# Sheet2.net
KiCad netlist of a schematic drawn in Altium Designer
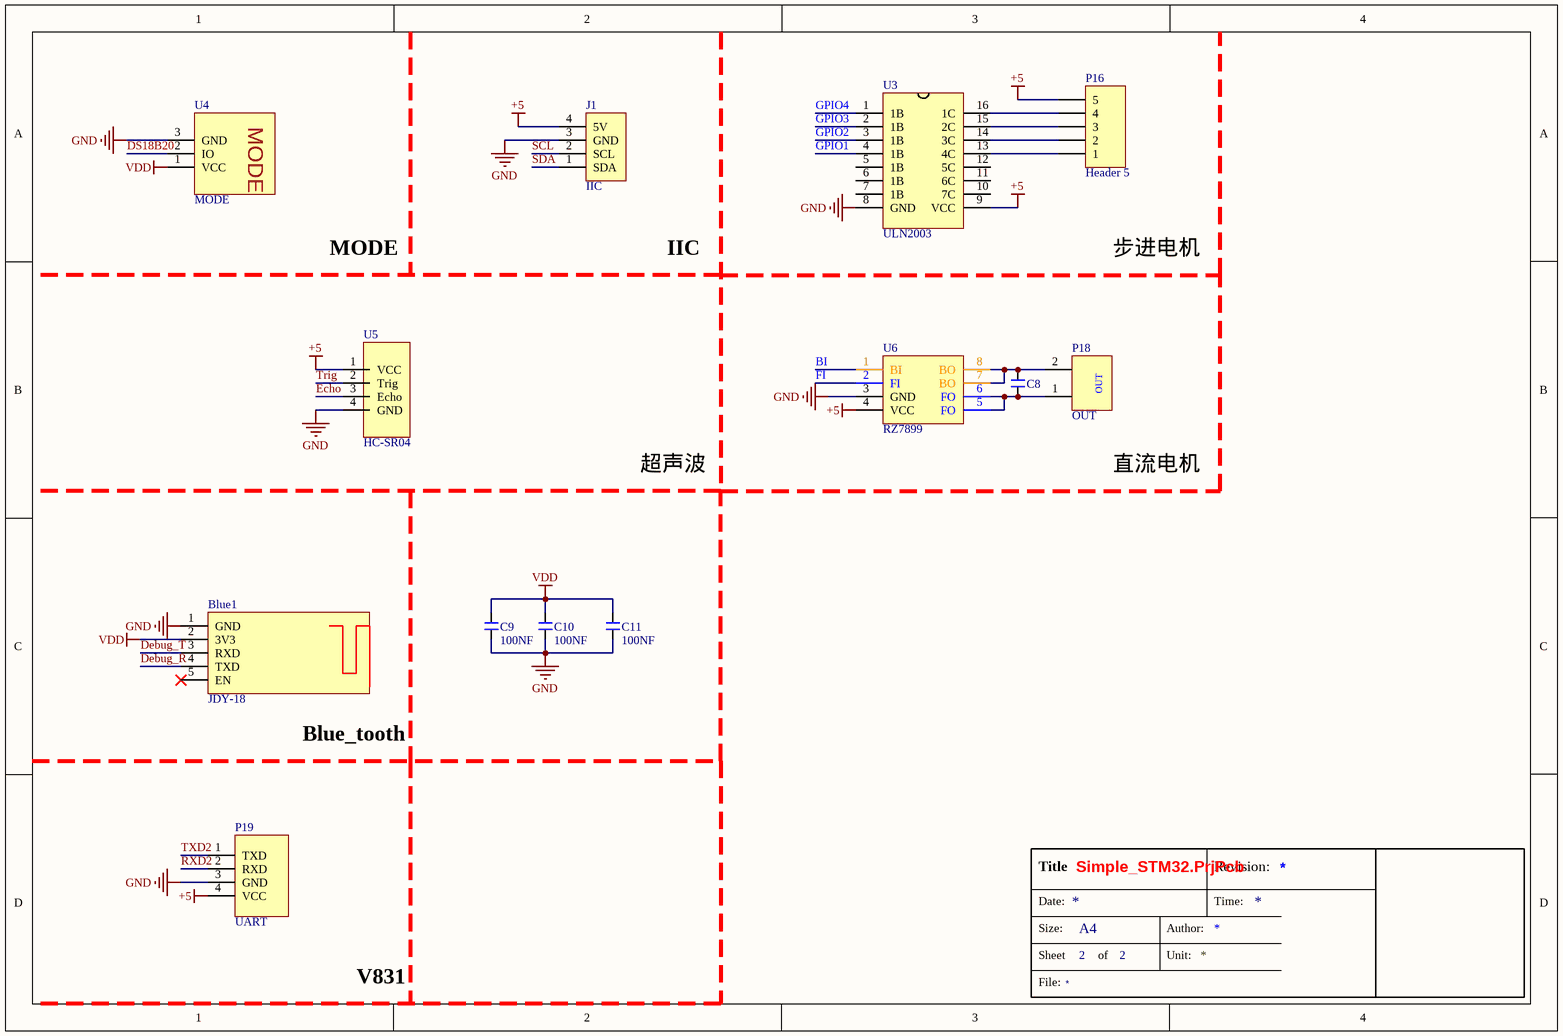
[diagram p0: Sheet2.SchDoc]

(export (version "E")
  (design (tool "Eeschema 10.0.6"))
  (components
    (comp (ref "Blue1")
      (value "JDY-18")
      (footprint "uart-Haerd")
      (description "MODE")
      (libsource (lib "User") (part "JDY-18"))
    )
    (comp (ref "C8")
      (value "100NF")
      (footprint "CAP_0603")
      (description "CAP  12~50V")
      (libsource (lib "User") (part "CAP"))
    )
    (comp (ref "C9")
      (value "100NF")
      (footprint "CAP_0603")
      (description "CAP  12~50V")
      (libsource (lib "User") (part "CAP"))
    )
    (comp (ref "C10")
      (value "100NF")
      (footprint "CAP_0603")
      (description "CAP  12~50V")
      (libsource (lib "User") (part "CAP"))
    )
    (comp (ref "C11")
      (value "100NF")
      (footprint "CAP_0603")
      (description "CAP  12~50V")
      (libsource (lib "User") (part "CAP"))
    )
    (comp (ref "J1")
      (value "IIC")
      (footprint "IIC-XH2.54-4PIN")
      (description "Heard")
      (libsource (lib "User") (part "IIC"))
    )
    (comp (ref "P16")
      (value "Header 5")
      (footprint "XH2.54-WI-5P")
      (description "Header, 5-Pin")
      (fields (field (name "PUBLISHER") "Altium Limited"))
      (libsource (lib "Miscellaneous Connectors") (part "Header 5"))
    )
    (comp (ref "P18")
      (value "OUT")
      (footprint "XH2.54-WI-2P")
      (description "Header")
      (libsource (lib "User") (part "OUT_2PIN"))
    )
    (comp (ref "P19")
      (value "UART")
      (footprint "UART")
      (description "Header")
      (libsource (lib "User") (part "UART"))
    )
    (comp (ref "U3")
      (value "ULN2003")
      (footprint "SOP16")
      (description "IC")
      (libsource (lib "User") (part "ULN2003"))
    )
    (comp (ref "U4") (value "MODE") (footprint "Header F 2.54X3") (libsource (lib "User") (part "MODE_3Pin")))
    (comp (ref "U5")
      (value "HC-SR04")
      (footprint "Ultrasonic")
      (description "Mode")
      (libsource (lib "User") (part "Ultrasonic"))
    )
    (comp (ref "U6")
      (value "RZ7899")
      (footprint "SOP_8_M")
      (description "Dreiv")
      (libsource (lib "User") (part "RZ7899"))
    )
  )
  (nets
    (net (code "1") (name "+5") (class "Default")
      (node (ref "J1") (pin "4") (pinfunction "5V_4") (pintype "passive"))
      (node (ref "P16") (pin "5") (pinfunction "5_5") (pintype "passive"))
      (node (ref "P19") (pin "4") (pinfunction "VCC_4") (pintype "passive"))
      (node (ref "U3") (pin "9") (pinfunction "VCC_9") (pintype "passive"))
      (node (ref "U5") (pin "1") (pinfunction "VCC_1") (pintype "passive"))
      (node (ref "U6") (pin "4") (pinfunction "VCC_4") (pintype "passive"))
    )
    (net (code "2") (name "/BI") (class "Default")
      (node (ref "U6") (pin "1") (pinfunction "BI_1") (pintype "passive"))
    )
    (net (code "3") (name "/DS18B20") (class "Default")
      (node (ref "U4") (pin "2") (pinfunction "IO_2") (pintype "passive"))
    )
    (net (code "4") (name "/Debug_R") (class "Default")
      (node (ref "Blue1") (pin "4") (pinfunction "TXD_4") (pintype "passive"))
    )
    (net (code "5") (name "/Debug_T") (class "Default")
      (node (ref "Blue1") (pin "3") (pinfunction "RXD_3") (pintype "passive"))
    )
    (net (code "6") (name "/Echo") (class "Default")
      (node (ref "U5") (pin "3") (pinfunction "Echo_3") (pintype "passive"))
    )
    (net (code "7") (name "/FI") (class "Default")
      (node (ref "U6") (pin "2") (pinfunction "FI_2") (pintype "passive"))
    )
    (net (code "8") (name "/GPIO1") (class "Default")
      (node (ref "U3") (pin "4") (pinfunction "1B_4") (pintype "passive"))
    )
    (net (code "9") (name "/GPIO2") (class "Default")
      (node (ref "U3") (pin "3") (pinfunction "1B_3") (pintype "passive"))
    )
    (net (code "10") (name "/GPIO3") (class "Default")
      (node (ref "U3") (pin "2") (pinfunction "1B_2") (pintype "passive"))
    )
    (net (code "11") (name "/GPIO4") (class "Default")
      (node (ref "U3") (pin "1") (pinfunction "1B_1") (pintype "passive"))
    )
    (net (code "12") (name "/RXD2") (class "Default")
      (node (ref "P19") (pin "2") (pinfunction "RXD_2") (pintype "passive"))
    )
    (net (code "13") (name "/SCL") (class "Default")
      (node (ref "J1") (pin "2") (pinfunction "SCL_2") (pintype "passive"))
    )
    (net (code "14") (name "/SDA") (class "Default")
      (node (ref "J1") (pin "1") (pinfunction "SDA_1") (pintype "passive"))
    )
    (net (code "15") (name "/TXD2") (class "Default")
      (node (ref "P19") (pin "1") (pinfunction "TXD_1") (pintype "passive"))
    )
    (net (code "16") (name "/Trig") (class "Default")
      (node (ref "U5") (pin "2") (pinfunction "Trig_2") (pintype "passive"))
    )
    (net (code "17") (name "GND") (class "Default")
      (node (ref "Blue1") (pin "1") (pinfunction "GND_1") (pintype "passive"))
      (node (ref "C10") (pin "1") (pinfunction "0_1") (pintype "passive"))
      (node (ref "C11") (pin "1") (pinfunction "0_1") (pintype "passive"))
      (node (ref "C9") (pin "1") (pinfunction "0_1") (pintype "passive"))
      (node (ref "J1") (pin "3") (pinfunction "GND_3") (pintype "passive"))
      (node (ref "P19") (pin "3") (pinfunction "GND_3") (pintype "passive"))
      (node (ref "U3") (pin "8") (pinfunction "GND_8") (pintype "passive"))
      (node (ref "U4") (pin "3") (pinfunction "GND_3") (pintype "passive"))
      (node (ref "U5") (pin "4") (pinfunction "GND_4") (pintype "passive"))
      (node (ref "U6") (pin "3") (pinfunction "GND_3") (pintype "passive"))
    )
    (net (code "18") (name "Net-(C8-0-Pad1)") (class "Default")
      (node (ref "C8") (pin "1") (pinfunction "0_1") (pintype "passive"))
      (node (ref "P18") (pin "1") (pintype "passive"))
      (node (ref "U6") (pin "5") (pinfunction "FO_5") (pintype "passive"))
      (node (ref "U6") (pin "6") (pinfunction "FO_6") (pintype "passive"))
    )
    (net (code "19") (name "Net-(C8-0-Pad2)") (class "Default")
      (node (ref "C8") (pin "2") (pinfunction "0_2") (pintype "passive"))
      (node (ref "P18") (pin "2") (pintype "passive"))
      (node (ref "U6") (pin "7") (pinfunction "BO_7") (pintype "passive"))
      (node (ref "U6") (pin "8") (pinfunction "BO_8") (pintype "passive"))
    )
    (net (code "20") (name "Net-(U3-1C)") (class "Default")
      (node (ref "P16") (pin "4") (pinfunction "4_4") (pintype "passive"))
      (node (ref "U3") (pin "16") (pinfunction "1C_16") (pintype "passive"))
    )
    (net (code "21") (name "Net-(U3-2C)") (class "Default")
      (node (ref "P16") (pin "3") (pinfunction "3_3") (pintype "passive"))
      (node (ref "U3") (pin "15") (pinfunction "2C_15") (pintype "passive"))
    )
    (net (code "22") (name "Net-(U3-3C)") (class "Default")
      (node (ref "P16") (pin "2") (pinfunction "2_2") (pintype "passive"))
      (node (ref "U3") (pin "14") (pinfunction "3C_14") (pintype "passive"))
    )
    (net (code "23") (name "Net-(U3-4C)") (class "Default")
      (node (ref "P16") (pin "1") (pinfunction "1_1") (pintype "passive"))
      (node (ref "U3") (pin "13") (pinfunction "4C_13") (pintype "passive"))
    )
    (net (code "24") (name "VDD") (class "Default")
      (node (ref "Blue1") (pin "2") (pinfunction "3V3_2") (pintype "passive"))
      (node (ref "C10") (pin "2") (pinfunction "0_2") (pintype "passive"))
      (node (ref "C11") (pin "2") (pinfunction "0_2") (pintype "passive"))
      (node (ref "C9") (pin "2") (pinfunction "0_2") (pintype "passive"))
      (node (ref "U4") (pin "1") (pinfunction "VCC_1") (pintype "passive"))
    )
    (net (code "25") (name "unconnected-(Blue1-EN-Pad5)") (class "Default")
      (node (ref "Blue1") (pin "5") (pinfunction "EN_5") (pintype "passive+no_connect"))
    )
    (net (code "26") (name "unconnected-(U3-1B-Pad5)") (class "Default")
      (node (ref "U3") (pin "5") (pinfunction "1B_5") (pintype "passive"))
    )
    (net (code "27") (name "unconnected-(U3-1B-Pad6)") (class "Default")
      (node (ref "U3") (pin "6") (pinfunction "1B_6") (pintype "passive"))
    )
    (net (code "28") (name "unconnected-(U3-1B-Pad7)") (class "Default")
      (node (ref "U3") (pin "7") (pinfunction "1B_7") (pintype "passive"))
    )
    (net (code "29") (name "unconnected-(U3-5C-Pad12)") (class "Default")
      (node (ref "U3") (pin "12") (pinfunction "5C_12") (pintype "passive"))
    )
    (net (code "30") (name "unconnected-(U3-6C-Pad11)") (class "Default")
      (node (ref "U3") (pin "11") (pinfunction "6C_11") (pintype "passive"))
    )
    (net (code "31") (name "unconnected-(U3-7C-Pad10)") (class "Default")
      (node (ref "U3") (pin "10") (pinfunction "7C_10") (pintype "passive"))
    )
  )
)
